# ECU_1.net
KiCad netlist of a schematic drawn in EAGLE
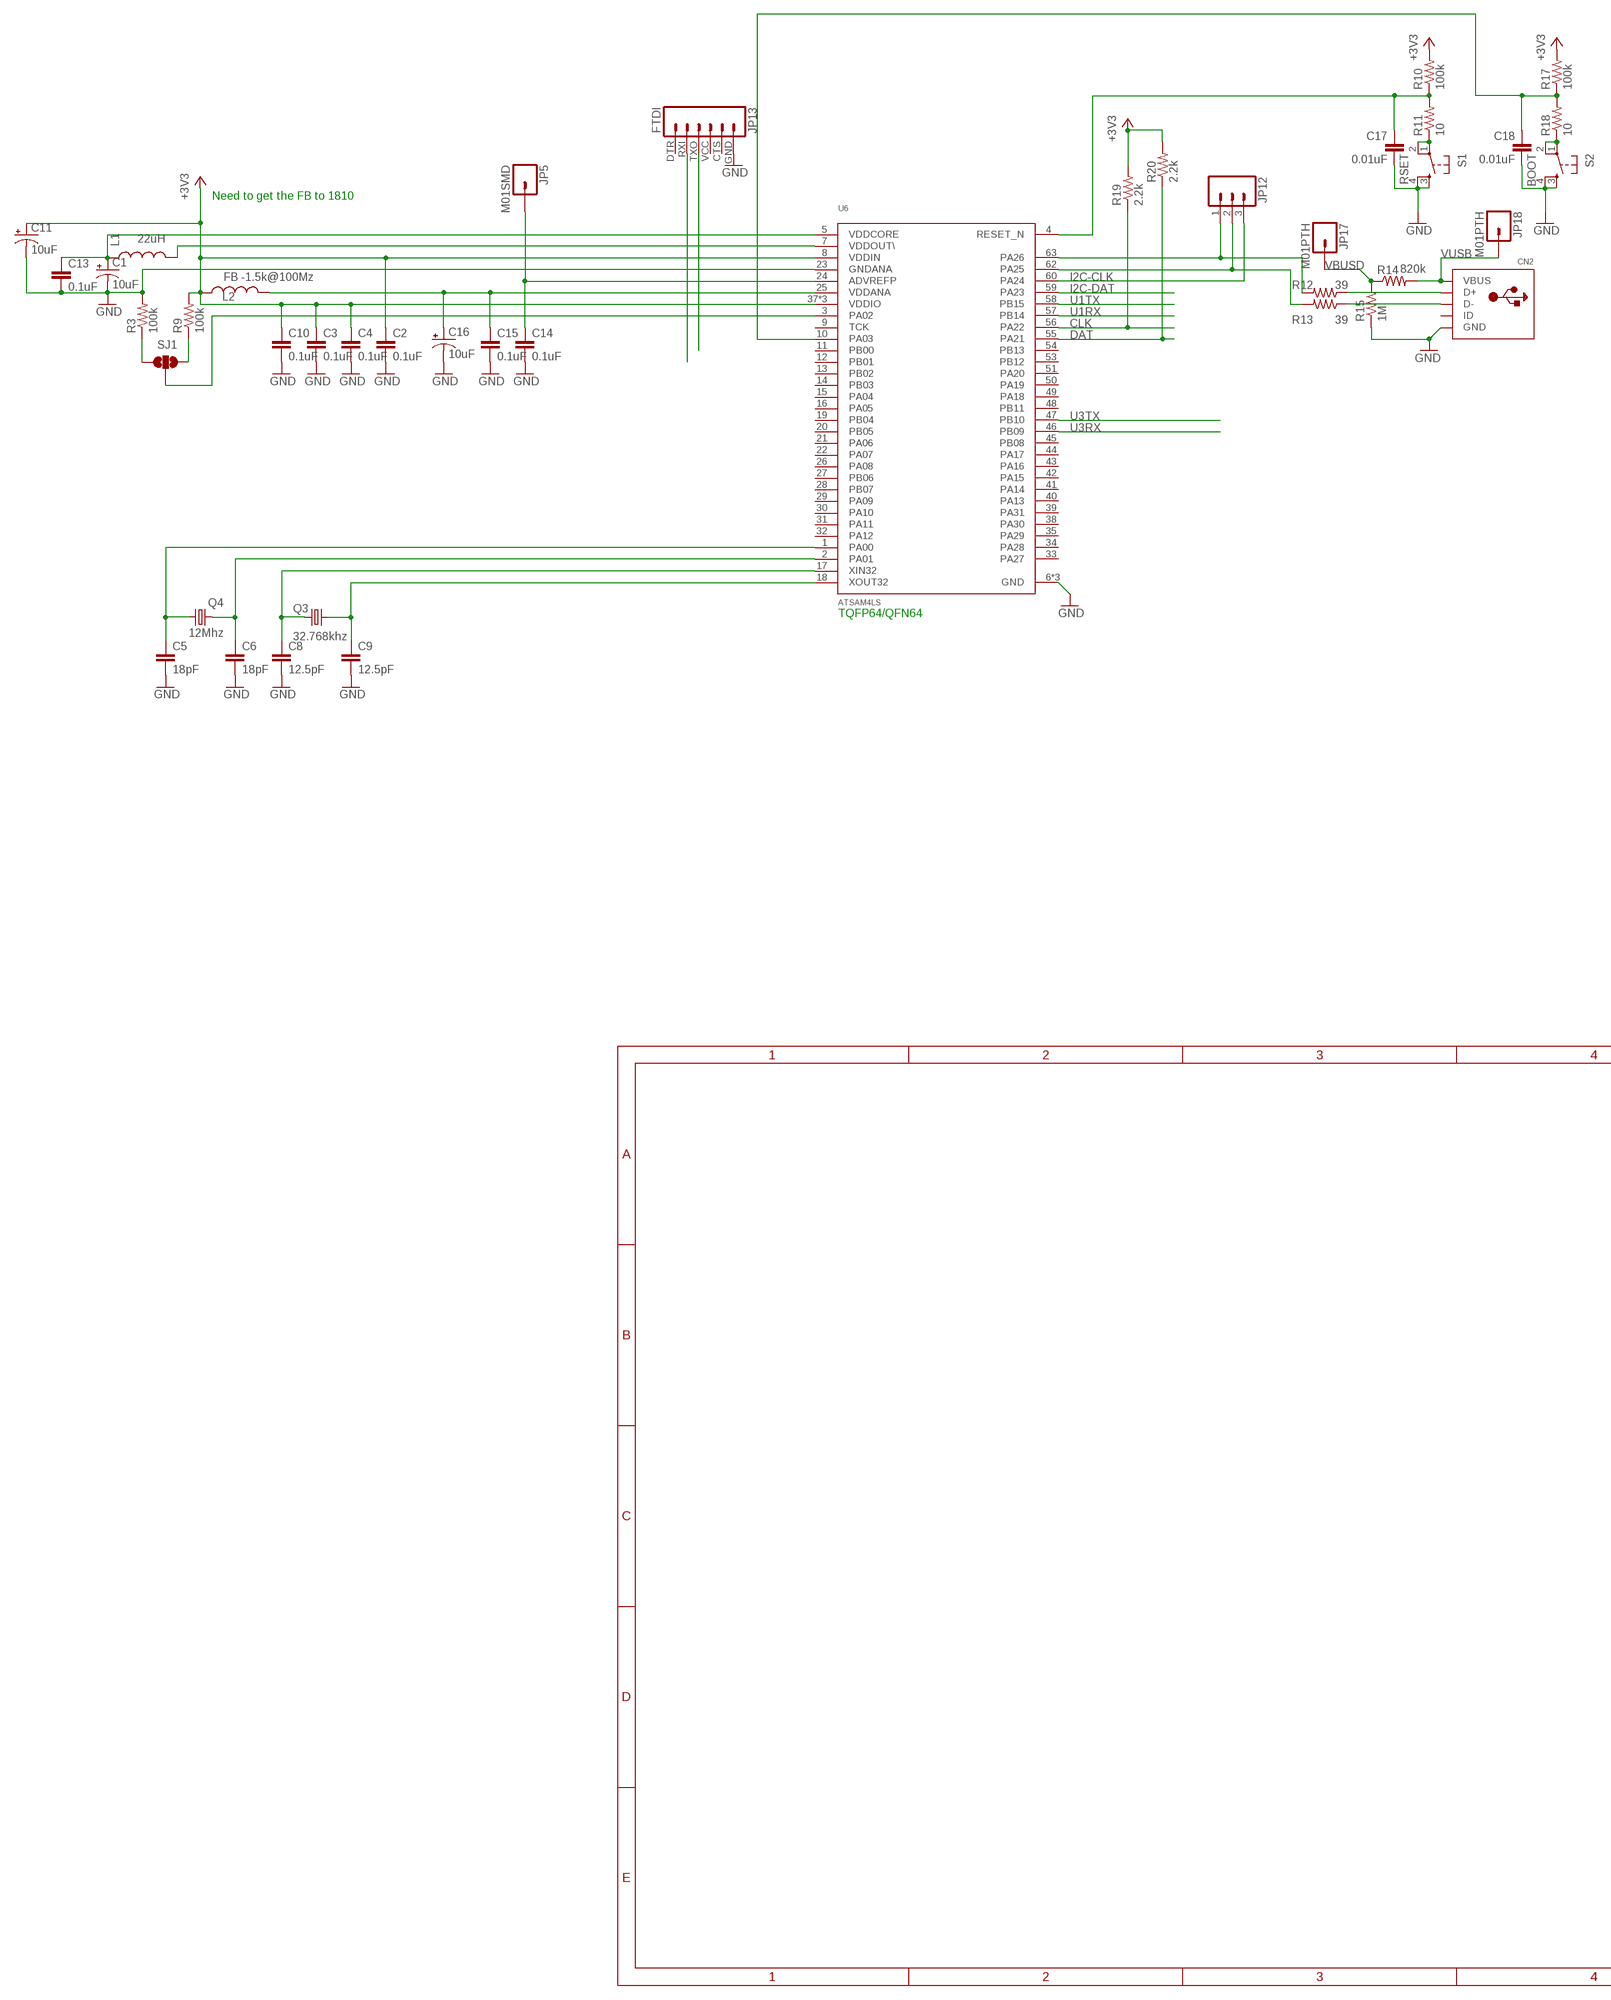
[diagram p0: schematic, sheet 1, part 1 of 2]
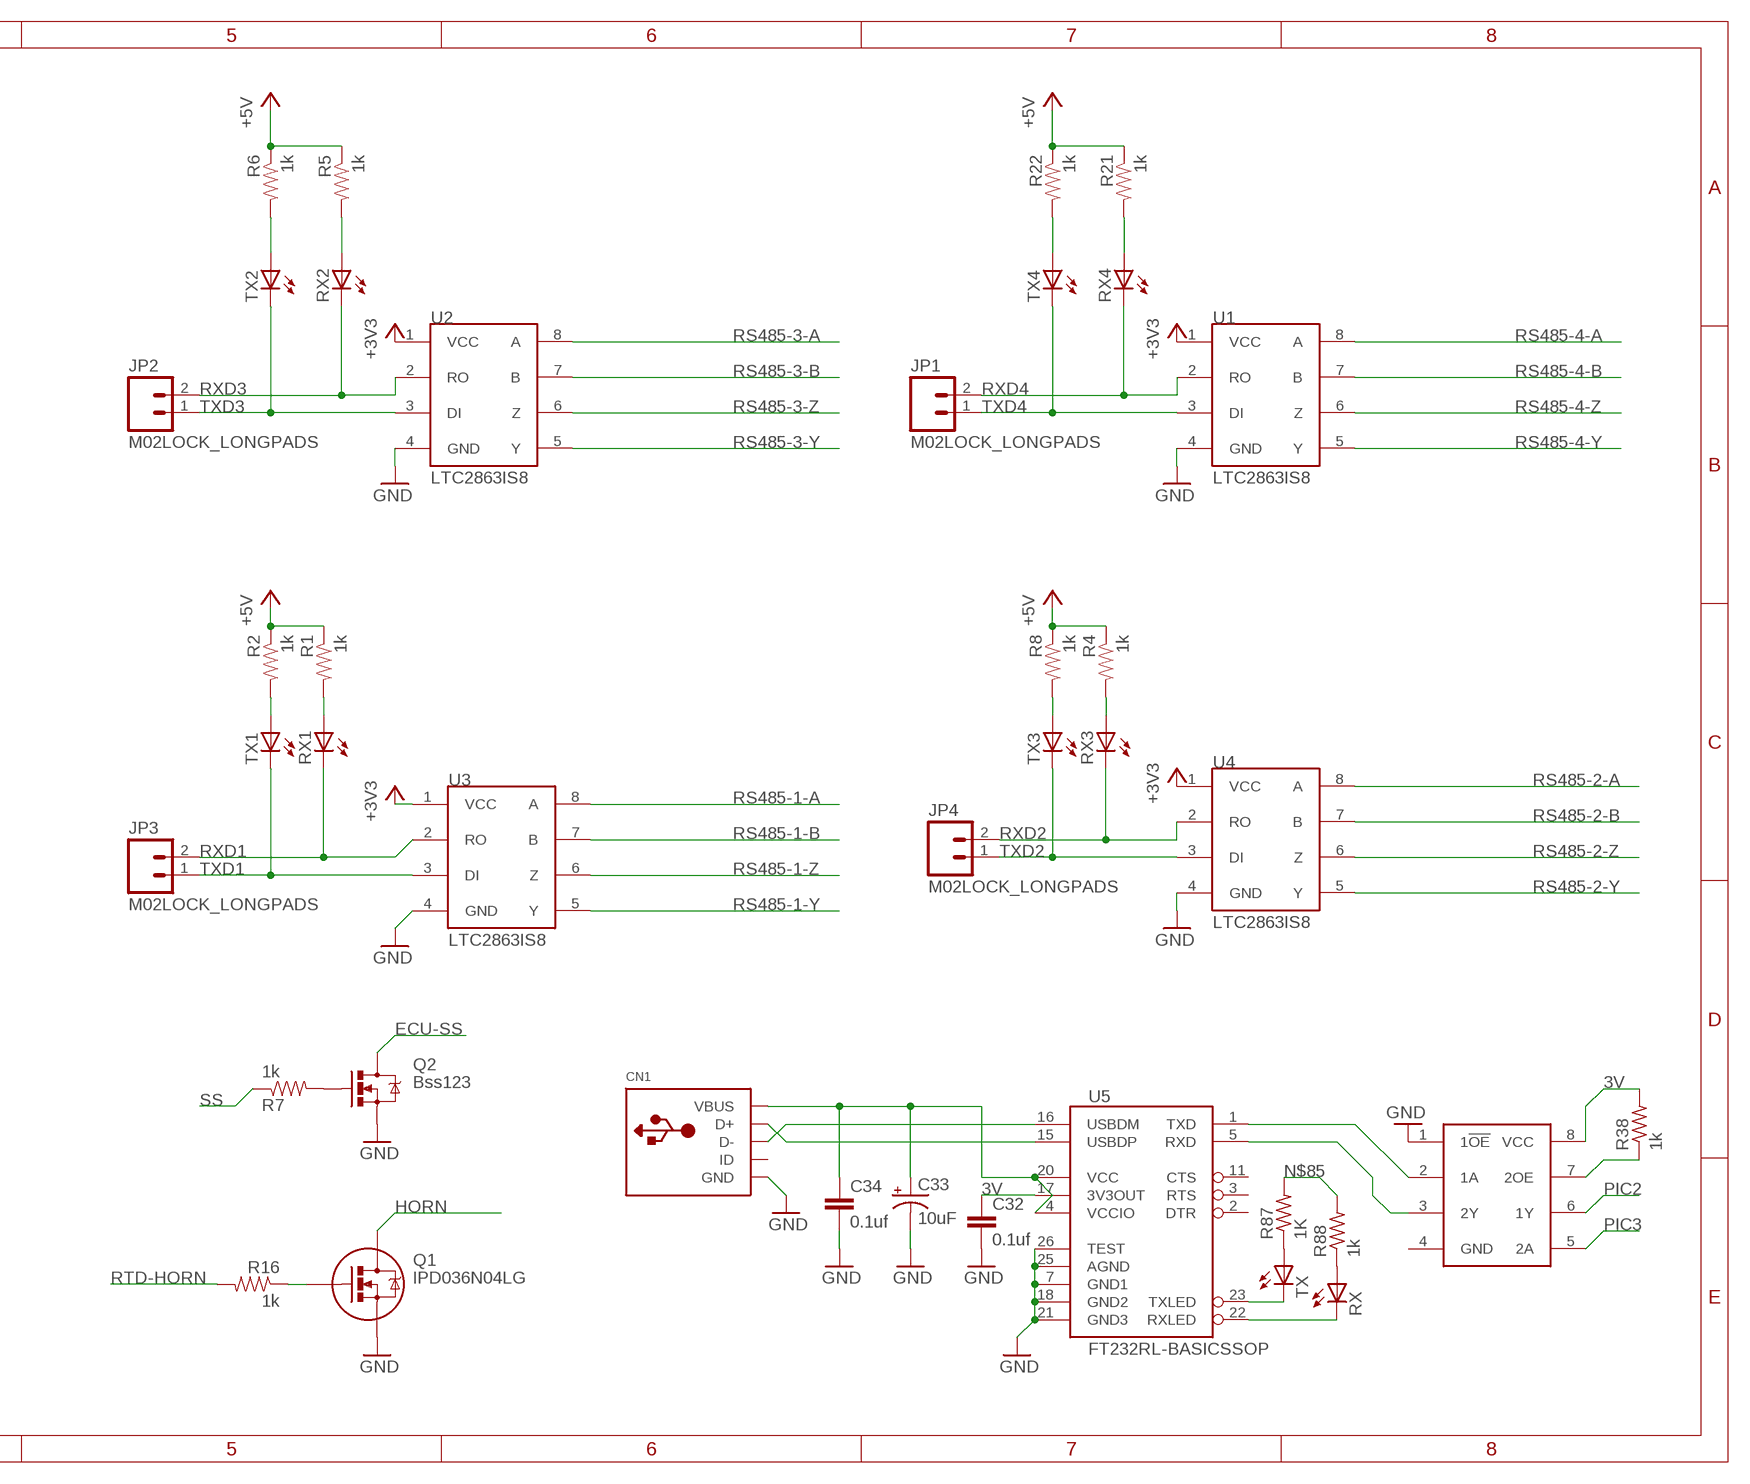
[diagram p1: schematic, sheet 1, part 2 of 2]
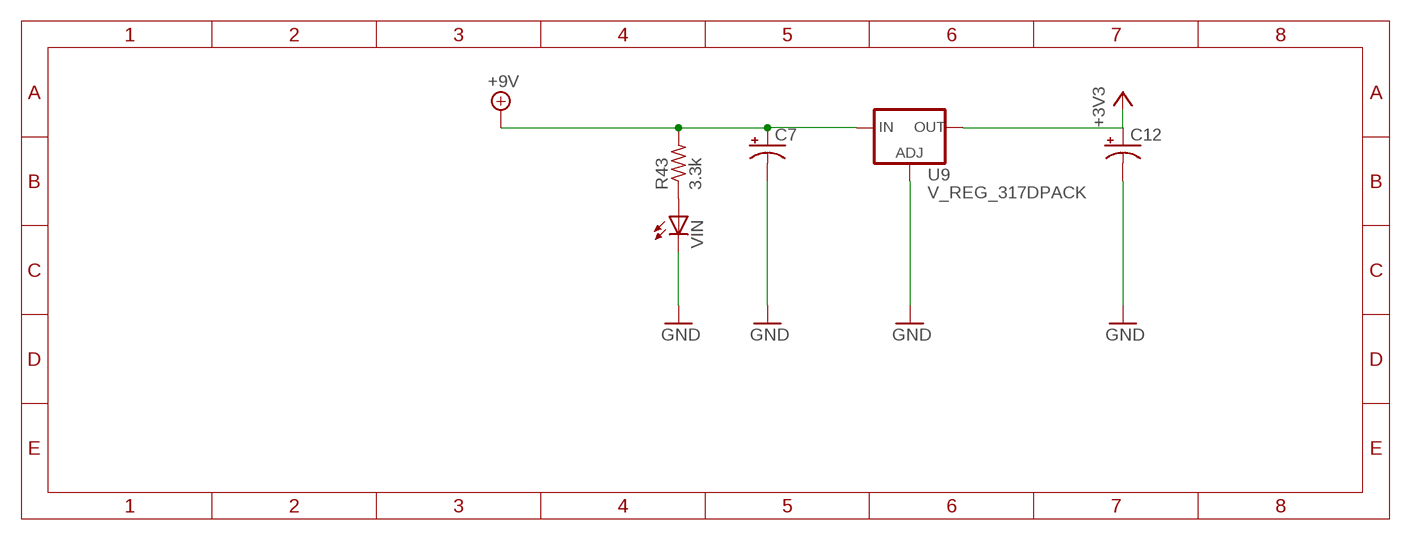
[diagram p2: schematic, sheet 2]
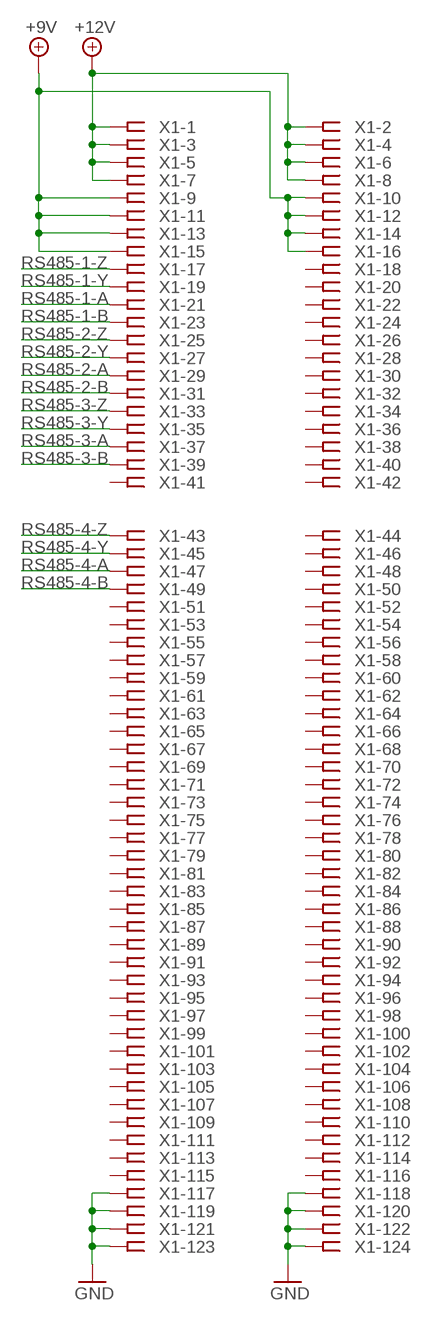
[diagram p3: schematic, sheet 3]

(export (version "E")
  (design (tool "Eeschema 10.0.6"))
  (components
    (comp (ref "C1")
      (value "10uF")
      (footprint "eagle-import:EIA3216")
      (libsource (lib "eagle-import") (part "SparkFun-Passives_CAP_POL1206"))
    )
    (comp (ref "C2")
      (value "0.1uF")
      (footprint "eagle-import:0805")
      (libsource (lib "eagle-import") (part "SparkFun-Passives_CAP0805"))
    )
    (comp (ref "C3")
      (value "0.1uF")
      (footprint "eagle-import:0805")
      (libsource (lib "eagle-import") (part "SparkFun-Passives_CAP0805"))
    )
    (comp (ref "C4")
      (value "0.1uF")
      (footprint "eagle-import:0805")
      (libsource (lib "eagle-import") (part "SparkFun-Passives_CAP0805"))
    )
    (comp (ref "C5")
      (value "18pF")
      (footprint "eagle-import:0805")
      (libsource (lib "eagle-import") (part "SparkFun-Passives_CAP0805"))
    )
    (comp (ref "C6")
      (value "18pF")
      (footprint "eagle-import:0805")
      (libsource (lib "eagle-import") (part "SparkFun-Passives_CAP0805"))
    )
    (comp (ref "C8")
      (value "12.5pF")
      (footprint "eagle-import:0805")
      (libsource (lib "eagle-import") (part "SparkFun-Passives_CAP0805"))
    )
    (comp (ref "C9")
      (value "12.5pF")
      (footprint "eagle-import:0805")
      (libsource (lib "eagle-import") (part "SparkFun-Passives_CAP0805"))
    )
    (comp (ref "C10")
      (value "0.1uF")
      (footprint "eagle-import:0805")
      (libsource (lib "eagle-import") (part "SparkFun-Passives_CAP0805"))
    )
    (comp (ref "C11")
      (value "10uF")
      (footprint "eagle-import:EIA3216")
      (libsource (lib "eagle-import") (part "10UF-16V-10%(TANT)"))
    )
    (comp (ref "C13")
      (value "0.1uF")
      (footprint "eagle-import:0805")
      (libsource (lib "eagle-import") (part "SparkFun-Passives_CAP0805"))
    )
    (comp (ref "C14")
      (value "0.1uF")
      (footprint "eagle-import:0805")
      (libsource (lib "eagle-import") (part "SparkFun-Passives_CAP0805"))
    )
    (comp (ref "C15")
      (value "0.1uF")
      (footprint "eagle-import:0805")
      (libsource (lib "eagle-import") (part "SparkFun-Passives_CAP0805"))
    )
    (comp (ref "C16")
      (value "10uF")
      (footprint "eagle-import:EIA3216")
      (libsource (lib "eagle-import") (part "SparkFun-Passives_CAP_POL1206"))
    )
    (comp (ref "C17")
      (value "0.01uF")
      (footprint "eagle-import:0805")
      (libsource (lib "eagle-import") (part "SparkFun-Passives_CAP0805"))
    )
    (comp (ref "C18")
      (value "0.01uF")
      (footprint "eagle-import:0805")
      (libsource (lib "eagle-import") (part "SparkFun-Passives_CAP0805"))
    )
    (comp (ref "C32")
      (value "0.1uf")
      (footprint "eagle-import:0805")
      (libsource (lib "eagle-import") (part "CAP0805"))
    )
    (comp (ref "C33")
      (value "10uF")
      (footprint "eagle-import:EIA3216")
      (libsource (lib "eagle-import") (part "CAP_POL1206"))
    )
    (comp (ref "C34")
      (value "0.1uf")
      (footprint "eagle-import:0805")
      (libsource (lib "eagle-import") (part "CAP0805"))
    )
    (comp (ref "CN1")
      (value "USBMOLEX")
      (footprint "eagle-import:USB-MINIB-THM-MOLEX")
      (libsource (lib "eagle-import") (part "USBMOLEX"))
    )
    (comp (ref "CN2")
      (value "USBMOLEX")
      (footprint "eagle-import:USB-MINIB-THM-MOLEX")
      (libsource (lib "eagle-import") (part "USBMOLEX"))
    )
    (comp (ref "JP1")
      (value "M02LOCK_LONGPADS")
      (footprint "eagle-import:1X02_LOCK_LONGPADS")
      (libsource (lib "eagle-import") (part "M02LOCK_LONGPADS"))
    )
    (comp (ref "JP2")
      (value "M02LOCK_LONGPADS")
      (footprint "eagle-import:1X02_LOCK_LONGPADS")
      (libsource (lib "eagle-import") (part "M02LOCK_LONGPADS"))
    )
    (comp (ref "JP3")
      (value "M02LOCK_LONGPADS")
      (footprint "eagle-import:1X02_LOCK_LONGPADS")
      (libsource (lib "eagle-import") (part "M02LOCK_LONGPADS"))
    )
    (comp (ref "JP4")
      (value "M02LOCK_LONGPADS")
      (footprint "eagle-import:1X02_LOCK_LONGPADS")
      (libsource (lib "eagle-import") (part "M02LOCK_LONGPADS"))
    )
    (comp (ref "JP5")
      (value "M01SMD")
      (footprint "eagle-import:LUXEON-PAD")
      (libsource (lib "eagle-import") (part "M01SMD"))
    )
    (comp (ref "JP12")
      (value "M03LOCK")
      (footprint "eagle-import:1X03_LOCK")
      (libsource (lib "eagle-import") (part "M03LOCK"))
    )
    (comp (ref "JP13")
      (value "FTDI")
      (footprint "eagle-import:FTDI_BASIC")
      (libsource (lib "eagle-import") (part "FTDI_BASICPTH"))
    )
    (comp (ref "JP17")
      (value "M01PTH")
      (footprint "eagle-import:1X01")
      (libsource (lib "eagle-import") (part "M01PTH"))
    )
    (comp (ref "JP18")
      (value "M01PTH")
      (footprint "eagle-import:1X01")
      (libsource (lib "eagle-import") (part "M01PTH"))
    )
    (comp (ref "L1")
      (value "22uH")
      (footprint "eagle-import:0805")
      (libsource (lib "eagle-import") (part "INDUCTOR0805"))
    )
    (comp (ref "L2")
      (value "FB -1.5k@100Mz")
      (footprint "eagle-import:0805")
      (libsource (lib "eagle-import") (part "INDUCTOR0805"))
    )
    (comp (ref "Q1")
      (value "IPD036N04LG")
      (footprint "eagle-import:TO-252")
      (libsource (lib "eagle-import") (part "IPD036N04LG"))
    )
    (comp (ref "Q2")
      (value "Bss123")
      (footprint "eagle-import:SOT23")
      (libsource (lib "eagle-import") (part "MOSFET-NCHANNELBSS123LT1G"))
    )
    (comp (ref "Q3")
      (value "32.768khz")
      (footprint "eagle-import:MM20SS")
      (libsource (lib "eagle-import") (part "CRYSTALMM20SS"))
    )
    (comp (ref "Q4")
      (value "12Mhz")
      (footprint "eagle-import:CTS406")
      (libsource (lib "eagle-import") (part "CRYSTALCTS406"))
    )
    (comp (ref "R1")
      (value "1k")
      (footprint "eagle-import:0805")
      (libsource (lib "eagle-import") (part "RESISTOR0805-RES"))
    )
    (comp (ref "R2")
      (value "1k")
      (footprint "eagle-import:0805")
      (libsource (lib "eagle-import") (part "RESISTOR0805-RES"))
    )
    (comp (ref "R3")
      (value "100k")
      (footprint "eagle-import:0805")
      (libsource (lib "eagle-import") (part "RESISTOR0805-RES"))
    )
    (comp (ref "R4")
      (value "1k")
      (footprint "eagle-import:0805")
      (libsource (lib "eagle-import") (part "RESISTOR0805-RES"))
    )
    (comp (ref "R5")
      (value "1k")
      (footprint "eagle-import:0805")
      (libsource (lib "eagle-import") (part "RESISTOR0805-RES"))
    )
    (comp (ref "R6")
      (value "1k")
      (footprint "eagle-import:0805")
      (libsource (lib "eagle-import") (part "RESISTOR0805-RES"))
    )
    (comp (ref "R7")
      (value "1k")
      (footprint "eagle-import:0805")
      (libsource (lib "eagle-import") (part "RESISTOR0805-RES"))
    )
    (comp (ref "R8")
      (value "1k")
      (footprint "eagle-import:0805")
      (libsource (lib "eagle-import") (part "RESISTOR0805-RES"))
    )
    (comp (ref "R9")
      (value "100k")
      (footprint "eagle-import:0805")
      (libsource (lib "eagle-import") (part "RESISTOR0805-RES"))
    )
    (comp (ref "R10")
      (value "100k")
      (footprint "eagle-import:0805")
      (libsource (lib "eagle-import") (part "RESISTOR0805-RES"))
    )
    (comp (ref "R11")
      (value "10")
      (footprint "eagle-import:0805")
      (libsource (lib "eagle-import") (part "RESISTOR0805-RES"))
    )
    (comp (ref "R12")
      (value "39")
      (footprint "eagle-import:0805")
      (libsource (lib "eagle-import") (part "RESISTOR0805-RES"))
    )
    (comp (ref "R13")
      (value "39")
      (footprint "eagle-import:0805")
      (libsource (lib "eagle-import") (part "RESISTOR0805-RES"))
    )
    (comp (ref "R14")
      (value "820k")
      (footprint "eagle-import:0805")
      (libsource (lib "eagle-import") (part "RESISTOR0805-RES"))
    )
    (comp (ref "R15")
      (value "1M")
      (footprint "eagle-import:0805")
      (libsource (lib "eagle-import") (part "RESISTOR0805-RES"))
    )
    (comp (ref "R16")
      (value "1k")
      (footprint "eagle-import:0805")
      (libsource (lib "eagle-import") (part "RESISTOR0805-RES"))
    )
    (comp (ref "R17")
      (value "100k")
      (footprint "eagle-import:0805")
      (libsource (lib "eagle-import") (part "RESISTOR0805-RES"))
    )
    (comp (ref "R18")
      (value "10")
      (footprint "eagle-import:0805")
      (libsource (lib "eagle-import") (part "RESISTOR0805-RES"))
    )
    (comp (ref "R19")
      (value "2.2k")
      (footprint "eagle-import:0805")
      (libsource (lib "eagle-import") (part "RESISTOR0805-RES"))
    )
    (comp (ref "R20")
      (value "2.2k")
      (footprint "eagle-import:0805")
      (libsource (lib "eagle-import") (part "RESISTOR0805-RES"))
    )
    (comp (ref "R21")
      (value "1k")
      (footprint "eagle-import:0805")
      (libsource (lib "eagle-import") (part "RESISTOR0805-RES"))
    )
    (comp (ref "R22")
      (value "1k")
      (footprint "eagle-import:0805")
      (libsource (lib "eagle-import") (part "RESISTOR0805-RES"))
    )
    (comp (ref "R38")
      (value "1k")
      (footprint "eagle-import:R0805")
      (libsource (lib "eagle-import") (part "R-US_R0805"))
    )
    (comp (ref "R87")
      (value "1K")
      (footprint "eagle-import:R0805")
      (libsource (lib "eagle-import") (part "R-US_R0805"))
    )
    (comp (ref "R88")
      (value "1k")
      (footprint "eagle-import:R0805")
      (libsource (lib "eagle-import") (part "R-US_R0805"))
    )
    (comp (ref "RX")
      (value "LEDCHIPLED_0805")
      (footprint "eagle-import:CHIPLED_0805")
      (libsource (lib "eagle-import") (part "LEDCHIPLED_0805"))
    )
    (comp (ref "RX1")
      (value "LEDCHIP-LED0805")
      (footprint "eagle-import:CHIP-LED0805")
      (libsource (lib "eagle-import") (part "LEDCHIP-LED0805"))
    )
    (comp (ref "RX2")
      (value "LEDCHIP-LED0805")
      (footprint "eagle-import:CHIP-LED0805")
      (libsource (lib "eagle-import") (part "LEDCHIP-LED0805"))
    )
    (comp (ref "RX3")
      (value "LEDCHIP-LED0805")
      (footprint "eagle-import:CHIP-LED0805")
      (libsource (lib "eagle-import") (part "LEDCHIP-LED0805"))
    )
    (comp (ref "RX4")
      (value "LEDCHIP-LED0805")
      (footprint "eagle-import:CHIP-LED0805")
      (libsource (lib "eagle-import") (part "LEDCHIP-LED0805"))
    )
    (comp (ref "S1")
      (value "RSET")
      (footprint "eagle-import:TACTILE-PTH")
      (libsource (lib "eagle-import") (part "TAC_SWITCHPTH"))
    )
    (comp (ref "S2")
      (value "BOOT")
      (footprint "eagle-import:TACTILE-PTH")
      (libsource (lib "eagle-import") (part "TAC_SWITCHPTH"))
    )
    (comp (ref "SJ1")
      (value "SOLDERJUMPER_2WAYS")
      (footprint "eagle-import:SJ_3")
      (libsource (lib "eagle-import") (part "SOLDERJUMPER_2WAYS"))
    )
    (comp (ref "TX")
      (value "LEDCHIPLED_0805")
      (footprint "eagle-import:CHIPLED_0805")
      (libsource (lib "eagle-import") (part "LEDCHIPLED_0805"))
    )
    (comp (ref "TX1")
      (value "LEDCHIP-LED0805")
      (footprint "eagle-import:CHIP-LED0805")
      (libsource (lib "eagle-import") (part "LEDCHIP-LED0805"))
    )
    (comp (ref "TX2")
      (value "LEDCHIP-LED0805")
      (footprint "eagle-import:CHIP-LED0805")
      (libsource (lib "eagle-import") (part "LEDCHIP-LED0805"))
    )
    (comp (ref "TX3")
      (value "LEDCHIP-LED0805")
      (footprint "eagle-import:CHIP-LED0805")
      (libsource (lib "eagle-import") (part "LEDCHIP-LED0805"))
    )
    (comp (ref "TX4")
      (value "LEDCHIP-LED0805")
      (footprint "eagle-import:CHIP-LED0805")
      (libsource (lib "eagle-import") (part "LEDCHIP-LED0805"))
    )
    (comp (ref "U1")
      (value "LTC2863IS8")
      (footprint "eagle-import:SO08")
      (libsource (lib "eagle-import") (part "ISL83077"))
    )
    (comp (ref "U2")
      (value "LTC2863IS8")
      (footprint "eagle-import:SO08")
      (libsource (lib "eagle-import") (part "ISL83077"))
    )
    (comp (ref "U3")
      (value "LTC2863IS8")
      (footprint "eagle-import:SO08")
      (libsource (lib "eagle-import") (part "ISL83077"))
    )
    (comp (ref "U4")
      (value "LTC2863IS8")
      (footprint "eagle-import:SO08")
      (libsource (lib "eagle-import") (part "ISL83077"))
    )
    (comp (ref "U5")
      (value "FT232RL-BASICSSOP")
      (footprint "eagle-import:SSOP28DB")
      (libsource (lib "eagle-import") (part "FT232RL-BASICSSOP"))
    )
    (comp (ref "U6")
      (value "ATSAM4LS")
      (footprint "eagle-import:TQFP-64")
      (libsource (lib "eagle-import") (part "SAM4L"))
    )
    (comp (ref "U14")
      (value "SN74LVC2G241DCTR")
      (footprint "eagle-import:VFSOP-8")
      (libsource (lib "eagle-import") (part "SN74LVC2G241DCTR"))
    )
    (comp (ref "C7")
      (value "CAP_POL7343")
      (footprint "eagle-import:EIA7343")
      (libsource (lib "eagle-import") (part "SparkFun-Capacitors_CAP_POL7343"))
    )
    (comp (ref "C12")
      (value "CAP_POL3528")
      (footprint "eagle-import:EIA3528")
      (libsource (lib "eagle-import") (part "SparkFun-Capacitors_CAP_POL3528"))
    )
    (comp (ref "R43")
      (value "3.3k")
      (footprint "eagle-import:R0805")
      (libsource (lib "eagle-import") (part "R-US_R0805"))
    )
    (comp (ref "U9")
      (value "V_REG_317DPACK")
      (footprint "eagle-import:V-REG_DPACK")
      (libsource (lib "eagle-import") (part "V_REG_317DPACK"))
    )
    (comp (ref "VIN")
      (value "LEDCHIP-LED0805")
      (footprint "eagle-import:CHIP-LED0805")
      (libsource (lib "eagle-import") (part "LEDCHIP-LED0805"))
    )
    (comp (ref "X1")
      (value "AGP-3X3")
      (footprint "eagle-import:AGP-3X3")
      (libsource (lib "eagle-import") (part "AGP-3X3"))
    )
  )
  (nets
    (net (code "1") (name "+3V3") (class "Default")
      (node (ref "C10") (pin "1") (pinfunction "1_1") (pintype "passive"))
      (node (ref "C11") (pin "A") (pinfunction "+_A") (pintype "passive"))
      (node (ref "C12") (pin "A") (pinfunction "+_A") (pintype "passive"))
      (node (ref "C2") (pin "1") (pinfunction "1_1") (pintype "passive"))
      (node (ref "C3") (pin "1") (pinfunction "1_1") (pintype "passive"))
      (node (ref "C4") (pin "1") (pinfunction "1_1") (pintype "passive"))
      (node (ref "L2") (pin "1") (pinfunction "1_1") (pintype "passive"))
      (node (ref "R10") (pin "2") (pinfunction "2_2") (pintype "passive"))
      (node (ref "R17") (pin "2") (pinfunction "2_2") (pintype "passive"))
      (node (ref "R19") (pin "2") (pinfunction "2_2") (pintype "passive"))
      (node (ref "R20") (pin "2") (pinfunction "2_2") (pintype "passive"))
      (node (ref "R9") (pin "2") (pinfunction "2_2") (pintype "passive"))
      (node (ref "U1") (pin "1") (pinfunction "VCC_1") (pintype "bidirectional"))
      (node (ref "U2") (pin "1") (pinfunction "VCC_1") (pintype "bidirectional"))
      (node (ref "U3") (pin "1") (pinfunction "VCC_1") (pintype "bidirectional"))
      (node (ref "U4") (pin "1") (pinfunction "VCC_1") (pintype "bidirectional"))
      (node (ref "U6") (pin "37") (pinfunction "VDDIO_37") (pintype "bidirectional"))
      (node (ref "U6") (pin "52") (pinfunction "VDDIO_52") (pintype "bidirectional"))
      (node (ref "U6") (pin "61") (pinfunction "VDDIO_61") (pintype "bidirectional"))
      (node (ref "U6") (pin "8") (pinfunction "VDDIN_8") (pintype "bidirectional"))
      (node (ref "U9") (pin "4") (pinfunction "OUT_4") (pintype "output"))
    )
    (net (code "2") (name "+5V") (class "Default")
      (node (ref "R1") (pin "1") (pinfunction "1_1") (pintype "passive"))
      (node (ref "R2") (pin "1") (pinfunction "1_1") (pintype "passive"))
      (node (ref "R21") (pin "1") (pinfunction "1_1") (pintype "passive"))
      (node (ref "R22") (pin "1") (pinfunction "1_1") (pintype "passive"))
      (node (ref "R4") (pin "1") (pinfunction "1_1") (pintype "passive"))
      (node (ref "R5") (pin "1") (pinfunction "1_1") (pintype "passive"))
      (node (ref "R6") (pin "1") (pinfunction "1_1") (pintype "passive"))
      (node (ref "R8") (pin "1") (pinfunction "1_1") (pintype "passive"))
    )
    (net (code "3") (name "+9V") (class "Default")
      (node (ref "C7") (pin "A") (pinfunction "+_A") (pintype "passive"))
      (node (ref "R43") (pin "2") (pinfunction "2_2") (pintype "passive"))
      (node (ref "U9") (pin "3") (pinfunction "IN_3") (pintype "input"))
      (node (ref "X1") (pin "10") (pinfunction "P_10") (pintype "passive"))
      (node (ref "X1") (pin "11") (pinfunction "P_11") (pintype "passive"))
      (node (ref "X1") (pin "12") (pinfunction "P_12") (pintype "passive"))
      (node (ref "X1") (pin "13") (pinfunction "P_13") (pintype "passive"))
      (node (ref "X1") (pin "14") (pinfunction "P_14") (pintype "passive"))
      (node (ref "X1") (pin "15") (pinfunction "P_15") (pintype "passive"))
      (node (ref "X1") (pin "16") (pinfunction "P_16") (pintype "passive"))
      (node (ref "X1") (pin "9") (pinfunction "P_9") (pintype "passive"))
    )
    (net (code "4") (name "+12V") (class "Default")
      (node (ref "X1") (pin "1") (pinfunction "P_1") (pintype "passive"))
      (node (ref "X1") (pin "2") (pinfunction "P_2") (pintype "passive"))
      (node (ref "X1") (pin "3") (pinfunction "P_3") (pintype "passive"))
      (node (ref "X1") (pin "4") (pinfunction "P_4") (pintype "passive"))
      (node (ref "X1") (pin "5") (pinfunction "P_5") (pintype "passive"))
      (node (ref "X1") (pin "6") (pinfunction "P_6") (pintype "passive"))
      (node (ref "X1") (pin "7") (pinfunction "P_7") (pintype "passive"))
      (node (ref "X1") (pin "8") (pinfunction "P_8") (pintype "passive"))
    )
    (net (code "5") (name "3V") (class "Default")
      (node (ref "C32") (pin "1") (pinfunction "1_1") (pintype "passive"))
      (node (ref "R38") (pin "2") (pinfunction "2_2") (pintype "passive"))
      (node (ref "U14") (pin "8") (pinfunction "VCC_8") (pintype "bidirectional"))
      (node (ref "U5") (pin "17") (pinfunction "3V3OUT_17") (pintype "output"))
    )
    (net (code "6") (name "CLK") (class "Default")
      (node (ref "R19") (pin "1") (pinfunction "1_1") (pintype "passive"))
      (node (ref "U6") (pin "56") (pinfunction "PA22_56") (pintype "bidirectional"))
    )
    (net (code "7") (name "DAT") (class "Default")
      (node (ref "R20") (pin "1") (pinfunction "1_1") (pintype "passive"))
      (node (ref "U6") (pin "55") (pinfunction "PA21_55") (pintype "bidirectional"))
    )
    (net (code "8") (name "ECU-SS") (class "Default")
      (node (ref "Q2") (pin "3") (pinfunction "D_3") (pintype "passive"))
    )
    (net (code "9") (name "GND") (class "Default")
      (node (ref "C1") (pin "C") (pinfunction "-_C") (pintype "passive"))
      (node (ref "C10") (pin "2") (pinfunction "2_2") (pintype "passive"))
      (node (ref "C11") (pin "C") (pinfunction "-_C") (pintype "passive"))
      (node (ref "C12") (pin "C") (pinfunction "-_C") (pintype "passive"))
      (node (ref "C13") (pin "2") (pinfunction "2_2") (pintype "passive"))
      (node (ref "C14") (pin "2") (pinfunction "2_2") (pintype "passive"))
      (node (ref "C15") (pin "2") (pinfunction "2_2") (pintype "passive"))
      (node (ref "C16") (pin "C") (pinfunction "-_C") (pintype "passive"))
      (node (ref "C17") (pin "2") (pinfunction "2_2") (pintype "passive"))
      (node (ref "C18") (pin "2") (pinfunction "2_2") (pintype "passive"))
      (node (ref "C2") (pin "2") (pinfunction "2_2") (pintype "passive"))
      (node (ref "C3") (pin "2") (pinfunction "2_2") (pintype "passive"))
      (node (ref "C32") (pin "2") (pinfunction "2_2") (pintype "passive"))
      (node (ref "C33") (pin "C") (pinfunction "-_C") (pintype "passive"))
      (node (ref "C34") (pin "2") (pinfunction "2_2") (pintype "passive"))
      (node (ref "C4") (pin "2") (pinfunction "2_2") (pintype "passive"))
      (node (ref "C5") (pin "2") (pinfunction "2_2") (pintype "passive"))
      (node (ref "C6") (pin "2") (pinfunction "2_2") (pintype "passive"))
      (node (ref "C7") (pin "C") (pinfunction "-_C") (pintype "passive"))
      (node (ref "C8") (pin "2") (pinfunction "2_2") (pintype "passive"))
      (node (ref "C9") (pin "2") (pinfunction "2_2") (pintype "passive"))
      (node (ref "CN1") (pin "GND") (pinfunction "GND_GND") (pintype "power_in"))
      (node (ref "CN2") (pin "GND") (pinfunction "GND_GND") (pintype "power_in"))
      (node (ref "JP13") (pin "GND") (pinfunction "6_GND") (pintype "passive"))
      (node (ref "Q1") (pin "3") (pinfunction "S_3") (pintype "passive"))
      (node (ref "Q2") (pin "2") (pinfunction "S_2") (pintype "passive"))
      (node (ref "R15") (pin "1") (pinfunction "1_1") (pintype "passive"))
      (node (ref "R3") (pin "2") (pinfunction "2_2") (pintype "passive"))
      (node (ref "S1") (pin "3") (pinfunction "3_3") (pintype "passive"))
      (node (ref "S1") (pin "4") (pinfunction "4_4") (pintype "passive"))
      (node (ref "S2") (pin "3") (pinfunction "3_3") (pintype "passive"))
      (node (ref "S2") (pin "4") (pinfunction "4_4") (pintype "passive"))
      (node (ref "U1") (pin "4") (pinfunction "GND_4") (pintype "bidirectional"))
      (node (ref "U14") (pin "1") (pinfunction "1~{OE}_1") (pintype "bidirectional"))
      (node (ref "U2") (pin "4") (pinfunction "GND_4") (pintype "bidirectional"))
      (node (ref "U3") (pin "4") (pinfunction "GND_4") (pintype "bidirectional"))
      (node (ref "U4") (pin "4") (pinfunction "GND_4") (pintype "bidirectional"))
      (node (ref "U5") (pin "18") (pinfunction "GND2_18") (pintype "power_in"))
      (node (ref "U5") (pin "21") (pinfunction "GND3_21") (pintype "power_in"))
      (node (ref "U5") (pin "25") (pinfunction "AGND_25") (pintype "power_in"))
      (node (ref "U5") (pin "26") (pinfunction "TEST_26") (pintype "input"))
      (node (ref "U5") (pin "7") (pinfunction "GND1_7") (pintype "power_in"))
      (node (ref "U6") (pin "23") (pinfunction "GNDANA_23") (pintype "bidirectional"))
      (node (ref "U6") (pin "36") (pinfunction "GND_36") (pintype "bidirectional"))
      (node (ref "U6") (pin "6") (pinfunction "GND_6") (pintype "bidirectional"))
      (node (ref "U6") (pin "64") (pinfunction "GND_64") (pintype "bidirectional"))
      (node (ref "U9") (pin "1") (pinfunction "ADJ_1") (pintype "input"))
      (node (ref "VIN") (pin "C") (pinfunction "C_C") (pintype "passive"))
      (node (ref "X1") (pin "117") (pinfunction "P_117") (pintype "passive"))
      (node (ref "X1") (pin "118") (pinfunction "P_118") (pintype "passive"))
      (node (ref "X1") (pin "119") (pinfunction "P_119") (pintype "passive"))
      (node (ref "X1") (pin "120") (pinfunction "P_120") (pintype "passive"))
      (node (ref "X1") (pin "121") (pinfunction "P_121") (pintype "passive"))
      (node (ref "X1") (pin "122") (pinfunction "P_122") (pintype "passive"))
      (node (ref "X1") (pin "123") (pinfunction "P_123") (pintype "passive"))
      (node (ref "X1") (pin "124") (pinfunction "P_124") (pintype "passive"))
    )
    (net (code "10") (name "HORN") (class "Default")
      (node (ref "Q1") (pin "2") (pinfunction "D_2") (pintype "passive"))
    )
    (net (code "11") (name "I2C-CLK") (class "Default")
      (node (ref "JP12") (pin "3") (pinfunction "3_3") (pintype "passive"))
      (node (ref "U6") (pin "60") (pinfunction "PA24_60") (pintype "bidirectional"))
    )
    (net (code "12") (name "I2C-DAT") (class "Default")
      (node (ref "U6") (pin "59") (pinfunction "PA23_59") (pintype "bidirectional"))
    )
    (net (code "13") (name "N$85") (class "Default")
      (node (ref "C33") (pin "A") (pinfunction "+_A") (pintype "passive"))
      (node (ref "C34") (pin "1") (pinfunction "1_1") (pintype "passive"))
      (node (ref "CN1") (pin "VBUS") (pinfunction "VBUS_VBUS") (pintype "power_in"))
      (node (ref "R87") (pin "2") (pinfunction "2_2") (pintype "passive"))
      (node (ref "R88") (pin "2") (pinfunction "2_2") (pintype "passive"))
      (node (ref "U5") (pin "20") (pinfunction "VCC_20") (pintype "power_in"))
      (node (ref "U5") (pin "4") (pinfunction "VCCIO_4") (pintype "power_in"))
    )
    (net (code "14") (name "Net-(C1-+)") (class "Default")
      (node (ref "C1") (pin "A") (pinfunction "+_A") (pintype "passive"))
      (node (ref "C13") (pin "1") (pinfunction "1_1") (pintype "passive"))
      (node (ref "L1") (pin "1") (pinfunction "1_1") (pintype "passive"))
      (node (ref "U6") (pin "5") (pinfunction "VDDCORE_5") (pintype "bidirectional"))
    )
    (net (code "15") (name "Net-(C16-+)") (class "Default")
      (node (ref "C15") (pin "1") (pinfunction "1_1") (pintype "passive"))
      (node (ref "C16") (pin "A") (pinfunction "+_A") (pintype "passive"))
      (node (ref "L2") (pin "2") (pinfunction "2_2") (pintype "passive"))
      (node (ref "U6") (pin "25") (pinfunction "VDDANA_25") (pintype "bidirectional"))
    )
    (net (code "16") (name "Net-(CN2-PadD+)") (class "Default")
      (node (ref "CN2") (pin "D+") (pinfunction "D+_D+") (pintype "bidirectional"))
      (node (ref "R12") (pin "1") (pinfunction "1_1") (pintype "passive"))
    )
    (net (code "17") (name "Net-(CN2-PadD-)") (class "Default")
      (node (ref "CN2") (pin "D-") (pinfunction "D-_D-") (pintype "bidirectional"))
      (node (ref "R13") (pin "1") (pinfunction "1_1") (pintype "passive"))
    )
    (net (code "18") (name "Net-(JP5-1)") (class "Default")
      (node (ref "C14") (pin "1") (pinfunction "1_1") (pintype "passive"))
      (node (ref "JP5") (pin "P$1") (pinfunction "1_P$1") (pintype "passive"))
      (node (ref "U6") (pin "24") (pinfunction "ADVREFP_24") (pintype "bidirectional"))
    )
    (net (code "19") (name "Net-(Q1-G)") (class "Default")
      (node (ref "Q1") (pin "1") (pinfunction "G_1") (pintype "passive"))
      (node (ref "R16") (pin "1") (pinfunction "1_1") (pintype "passive"))
    )
    (net (code "20") (name "Net-(Q2-G)") (class "Default")
      (node (ref "Q2") (pin "1") (pinfunction "G_1") (pintype "passive"))
      (node (ref "R7") (pin "2") (pinfunction "2_2") (pintype "passive"))
    )
    (net (code "21") (name "Net-(Q3-2)") (class "Default")
      (node (ref "C9") (pin "1") (pinfunction "1_1") (pintype "passive"))
      (node (ref "Q3") (pin "4") (pinfunction "2_4") (pintype "passive"))
      (node (ref "U6") (pin "18") (pinfunction "XOUT32_18") (pintype "bidirectional"))
    )
    (net (code "22") (name "Net-(Q4-2)") (class "Default")
      (node (ref "C5") (pin "1") (pinfunction "1_1") (pintype "passive"))
      (node (ref "Q4") (pin "3") (pinfunction "2_3") (pintype "passive"))
      (node (ref "U6") (pin "1") (pinfunction "PA00_1") (pintype "bidirectional"))
    )
    (net (code "23") (name "Net-(R1-Pad2)") (class "Default")
      (node (ref "R1") (pin "2") (pinfunction "2_2") (pintype "passive"))
      (node (ref "RX1") (pin "A") (pinfunction "A_A") (pintype "passive"))
    )
    (net (code "24") (name "Net-(R2-Pad2)") (class "Default")
      (node (ref "R2") (pin "2") (pinfunction "2_2") (pintype "passive"))
      (node (ref "TX1") (pin "A") (pinfunction "A_A") (pintype "passive"))
    )
    (net (code "25") (name "Net-(R3-Pad1)") (class "Default")
      (node (ref "R3") (pin "1") (pinfunction "1_1") (pintype "passive"))
      (node (ref "SJ1") (pin "3") (pinfunction "3_3") (pintype "passive"))
    )
    (net (code "26") (name "Net-(R4-Pad2)") (class "Default")
      (node (ref "R4") (pin "2") (pinfunction "2_2") (pintype "passive"))
      (node (ref "RX3") (pin "A") (pinfunction "A_A") (pintype "passive"))
    )
    (net (code "27") (name "Net-(R5-Pad2)") (class "Default")
      (node (ref "R5") (pin "2") (pinfunction "2_2") (pintype "passive"))
      (node (ref "RX2") (pin "A") (pinfunction "A_A") (pintype "passive"))
    )
    (net (code "28") (name "Net-(R6-Pad2)") (class "Default")
      (node (ref "R6") (pin "2") (pinfunction "2_2") (pintype "passive"))
      (node (ref "TX2") (pin "A") (pinfunction "A_A") (pintype "passive"))
    )
    (net (code "29") (name "Net-(R8-Pad2)") (class "Default")
      (node (ref "R8") (pin "2") (pinfunction "2_2") (pintype "passive"))
      (node (ref "TX3") (pin "A") (pinfunction "A_A") (pintype "passive"))
    )
    (net (code "30") (name "Net-(R9-Pad1)") (class "Default")
      (node (ref "R9") (pin "1") (pinfunction "1_1") (pintype "passive"))
      (node (ref "SJ1") (pin "1") (pinfunction "1_1") (pintype "passive"))
    )
    (net (code "31") (name "Net-(R11-Pad1)") (class "Default")
      (node (ref "R11") (pin "1") (pinfunction "1_1") (pintype "passive"))
      (node (ref "S1") (pin "1") (pinfunction "1_1") (pintype "passive"))
      (node (ref "S1") (pin "2") (pinfunction "2_2") (pintype "passive"))
    )
    (net (code "32") (name "Net-(R18-Pad1)") (class "Default")
      (node (ref "R18") (pin "1") (pinfunction "1_1") (pintype "passive"))
      (node (ref "S2") (pin "1") (pinfunction "1_1") (pintype "passive"))
      (node (ref "S2") (pin "2") (pinfunction "2_2") (pintype "passive"))
    )
    (net (code "33") (name "Net-(R21-Pad2)") (class "Default")
      (node (ref "R21") (pin "2") (pinfunction "2_2") (pintype "passive"))
      (node (ref "RX4") (pin "A") (pinfunction "A_A") (pintype "passive"))
    )
    (net (code "34") (name "Net-(R22-Pad2)") (class "Default")
      (node (ref "R22") (pin "2") (pinfunction "2_2") (pintype "passive"))
      (node (ref "TX4") (pin "A") (pinfunction "A_A") (pintype "passive"))
    )
    (net (code "35") (name "Net-(R43-Pad1)") (class "Default")
      (node (ref "R43") (pin "1") (pinfunction "1_1") (pintype "passive"))
      (node (ref "VIN") (pin "A") (pinfunction "A_A") (pintype "passive"))
    )
    (net (code "36") (name "Net-(R87-Pad1)") (class "Default")
      (node (ref "R87") (pin "1") (pinfunction "1_1") (pintype "passive"))
      (node (ref "TX") (pin "A") (pinfunction "A_A") (pintype "passive"))
    )
    (net (code "37") (name "Net-(R88-Pad1)") (class "Default")
      (node (ref "R88") (pin "1") (pinfunction "1_1") (pintype "passive"))
      (node (ref "RX") (pin "A") (pinfunction "A_A") (pintype "passive"))
    )
    (net (code "38") (name "Net-(U5-RXLED)") (class "Default")
      (node (ref "RX") (pin "C") (pinfunction "C_C") (pintype "passive"))
      (node (ref "U5") (pin "22") (pinfunction "RXLED_22") (pintype "bidirectional"))
    )
    (net (code "39") (name "Net-(U5-TXLED)") (class "Default")
      (node (ref "TX") (pin "C") (pinfunction "C_C") (pintype "passive"))
      (node (ref "U5") (pin "23") (pinfunction "TXLED_23") (pintype "bidirectional"))
    )
    (net (code "40") (name "Net-(U5-USBDM)") (class "Default")
      (node (ref "CN1") (pin "D-") (pinfunction "D-_D-") (pintype "bidirectional"))
      (node (ref "U5") (pin "16") (pinfunction "USBDM_16") (pintype "bidirectional"))
    )
    (net (code "41") (name "Net-(U5-USBDP)") (class "Default")
      (node (ref "CN1") (pin "D+") (pinfunction "D+_D+") (pintype "bidirectional"))
      (node (ref "U5") (pin "15") (pinfunction "USBDP_15") (pintype "bidirectional"))
    )
    (net (code "42") (name "Net-(U6-PA01)") (class "Default")
      (node (ref "C6") (pin "1") (pinfunction "1_1") (pintype "passive"))
      (node (ref "Q4") (pin "1") (pinfunction "1_1") (pintype "passive"))
      (node (ref "U6") (pin "2") (pinfunction "PA01_2") (pintype "bidirectional"))
    )
    (net (code "43") (name "Net-(U6-PA02)") (class "Default")
      (node (ref "SJ1") (pin "2") (pinfunction "2_2") (pintype "passive"))
      (node (ref "U6") (pin "3") (pinfunction "PA02_3") (pintype "bidirectional"))
    )
    (net (code "44") (name "Net-(U6-PA03)") (class "Default")
      (node (ref "C18") (pin "1") (pinfunction "1_1") (pintype "passive"))
      (node (ref "R17") (pin "1") (pinfunction "1_1") (pintype "passive"))
      (node (ref "R18") (pin "2") (pinfunction "2_2") (pintype "passive"))
      (node (ref "U6") (pin "10") (pinfunction "PA03_10") (pintype "bidirectional"))
    )
    (net (code "45") (name "Net-(U6-PA25)") (class "Default")
      (node (ref "JP12") (pin "2") (pinfunction "2_2") (pintype "passive"))
      (node (ref "R13") (pin "2") (pinfunction "2_2") (pintype "passive"))
      (node (ref "U6") (pin "62") (pinfunction "PA25_62") (pintype "bidirectional"))
    )
    (net (code "46") (name "Net-(U6-PA26)") (class "Default")
      (node (ref "JP12") (pin "1") (pinfunction "1_1") (pintype "passive"))
      (node (ref "R12") (pin "2") (pinfunction "2_2") (pintype "passive"))
      (node (ref "U6") (pin "63") (pinfunction "PA26_63") (pintype "bidirectional"))
    )
    (net (code "47") (name "Net-(U6-RESET_N)") (class "Default")
      (node (ref "C17") (pin "1") (pinfunction "1_1") (pintype "passive"))
      (node (ref "R10") (pin "1") (pinfunction "1_1") (pintype "passive"))
      (node (ref "R11") (pin "2") (pinfunction "2_2") (pintype "passive"))
      (node (ref "U6") (pin "4") (pinfunction "RESET_N_4") (pintype "bidirectional"))
    )
    (net (code "48") (name "Net-(U6-VDDOUT\\)") (class "Default")
      (node (ref "L1") (pin "2") (pinfunction "2_2") (pintype "passive"))
      (node (ref "U6") (pin "7") (pinfunction "VDDOUT\\_7") (pintype "bidirectional"))
    )
    (net (code "49") (name "Net-(U6-XIN32)") (class "Default")
      (node (ref "C8") (pin "1") (pinfunction "1_1") (pintype "passive"))
      (node (ref "Q3") (pin "1") (pinfunction "1_1") (pintype "passive"))
      (node (ref "U6") (pin "17") (pinfunction "XIN32_17") (pintype "bidirectional"))
    )
    (net (code "50") (name "Net-(U14-1A)") (class "Default")
      (node (ref "U14") (pin "2") (pinfunction "1A_2") (pintype "bidirectional"))
      (node (ref "U5") (pin "1") (pinfunction "TXD_1") (pintype "output"))
    )
    (net (code "51") (name "Net-(U14-2OE)") (class "Default")
      (node (ref "R38") (pin "1") (pinfunction "1_1") (pintype "passive"))
      (node (ref "U14") (pin "7") (pinfunction "2OE_7") (pintype "bidirectional"))
    )
    (net (code "52") (name "Net-(U14-2Y)") (class "Default")
      (node (ref "U14") (pin "3") (pinfunction "2Y_3") (pintype "bidirectional"))
      (node (ref "U5") (pin "5") (pinfunction "RXD_5") (pintype "input"))
    )
    (net (code "53") (name "PIC2") (class "Default")
      (node (ref "U14") (pin "6") (pinfunction "1Y_6") (pintype "bidirectional"))
    )
    (net (code "54") (name "PIC3") (class "Default")
      (node (ref "U14") (pin "5") (pinfunction "2A_5") (pintype "bidirectional"))
    )
    (net (code "55") (name "RS485-1-A") (class "Default")
      (node (ref "U3") (pin "8") (pinfunction "A_8") (pintype "bidirectional"))
      (node (ref "X1") (pin "21") (pinfunction "P_21") (pintype "passive"))
    )
    (net (code "56") (name "RS485-1-B") (class "Default")
      (node (ref "U3") (pin "7") (pinfunction "B_7") (pintype "bidirectional"))
      (node (ref "X1") (pin "23") (pinfunction "P_23") (pintype "passive"))
    )
    (net (code "57") (name "RS485-1-Y") (class "Default")
      (node (ref "U3") (pin "5") (pinfunction "Y_5") (pintype "bidirectional"))
      (node (ref "X1") (pin "19") (pinfunction "P_19") (pintype "passive"))
    )
    (net (code "58") (name "RS485-1-Z") (class "Default")
      (node (ref "U3") (pin "6") (pinfunction "Z_6") (pintype "bidirectional"))
      (node (ref "X1") (pin "17") (pinfunction "P_17") (pintype "passive"))
    )
    (net (code "59") (name "RS485-2-A") (class "Default")
      (node (ref "U4") (pin "8") (pinfunction "A_8") (pintype "bidirectional"))
      (node (ref "X1") (pin "29") (pinfunction "P_29") (pintype "passive"))
    )
    (net (code "60") (name "RS485-2-B") (class "Default")
      (node (ref "U4") (pin "7") (pinfunction "B_7") (pintype "bidirectional"))
      (node (ref "X1") (pin "31") (pinfunction "P_31") (pintype "passive"))
    )
    (net (code "61") (name "RS485-2-Y") (class "Default")
      (node (ref "U4") (pin "5") (pinfunction "Y_5") (pintype "bidirectional"))
      (node (ref "X1") (pin "27") (pinfunction "P_27") (pintype "passive"))
    )
    (net (code "62") (name "RS485-2-Z") (class "Default")
      (node (ref "U4") (pin "6") (pinfunction "Z_6") (pintype "bidirectional"))
      (node (ref "X1") (pin "25") (pinfunction "P_25") (pintype "passive"))
    )
    (net (code "63") (name "RS485-3-A") (class "Default")
      (node (ref "U2") (pin "8") (pinfunction "A_8") (pintype "bidirectional"))
      (node (ref "X1") (pin "37") (pinfunction "P_37") (pintype "passive"))
    )
    (net (code "64") (name "RS485-3-B") (class "Default")
      (node (ref "U2") (pin "7") (pinfunction "B_7") (pintype "bidirectional"))
      (node (ref "X1") (pin "39") (pinfunction "P_39") (pintype "passive"))
    )
    (net (code "65") (name "RS485-3-Y") (class "Default")
      (node (ref "U2") (pin "5") (pinfunction "Y_5") (pintype "bidirectional"))
      (node (ref "X1") (pin "35") (pinfunction "P_35") (pintype "passive"))
    )
    (net (code "66") (name "RS485-3-Z") (class "Default")
      (node (ref "U2") (pin "6") (pinfunction "Z_6") (pintype "bidirectional"))
      (node (ref "X1") (pin "33") (pinfunction "P_33") (pintype "passive"))
    )
    (net (code "67") (name "RS485-4-A") (class "Default")
      (node (ref "U1") (pin "8") (pinfunction "A_8") (pintype "bidirectional"))
      (node (ref "X1") (pin "47") (pinfunction "P_47") (pintype "passive"))
    )
    (net (code "68") (name "RS485-4-B") (class "Default")
      (node (ref "U1") (pin "7") (pinfunction "B_7") (pintype "bidirectional"))
      (node (ref "X1") (pin "49") (pinfunction "P_49") (pintype "passive"))
    )
    (net (code "69") (name "RS485-4-Y") (class "Default")
      (node (ref "U1") (pin "5") (pinfunction "Y_5") (pintype "bidirectional"))
      (node (ref "X1") (pin "45") (pinfunction "P_45") (pintype "passive"))
    )
    (net (code "70") (name "RS485-4-Z") (class "Default")
      (node (ref "U1") (pin "6") (pinfunction "Z_6") (pintype "bidirectional"))
      (node (ref "X1") (pin "43") (pinfunction "P_43") (pintype "passive"))
    )
    (net (code "71") (name "RTD-HORN") (class "Default")
      (node (ref "R16") (pin "2") (pinfunction "2_2") (pintype "passive"))
    )
    (net (code "72") (name "RXD1") (class "Default")
      (node (ref "JP3") (pin "2") (pinfunction "2_2") (pintype "passive"))
      (node (ref "RX1") (pin "C") (pinfunction "C_C") (pintype "passive"))
      (node (ref "U3") (pin "2") (pinfunction "RO_2") (pintype "bidirectional"))
    )
    (net (code "73") (name "RXD2") (class "Default")
      (node (ref "JP4") (pin "2") (pinfunction "2_2") (pintype "passive"))
      (node (ref "RX3") (pin "C") (pinfunction "C_C") (pintype "passive"))
      (node (ref "U4") (pin "2") (pinfunction "RO_2") (pintype "bidirectional"))
    )
    (net (code "74") (name "RXD3") (class "Default")
      (node (ref "JP2") (pin "2") (pinfunction "2_2") (pintype "passive"))
      (node (ref "RX2") (pin "C") (pinfunction "C_C") (pintype "passive"))
      (node (ref "U2") (pin "2") (pinfunction "RO_2") (pintype "bidirectional"))
    )
    (net (code "75") (name "RXD4") (class "Default")
      (node (ref "JP1") (pin "2") (pinfunction "2_2") (pintype "passive"))
      (node (ref "RX4") (pin "C") (pinfunction "C_C") (pintype "passive"))
      (node (ref "U1") (pin "2") (pinfunction "RO_2") (pintype "bidirectional"))
    )
    (net (code "76") (name "SS") (class "Default")
      (node (ref "R7") (pin "1") (pinfunction "1_1") (pintype "passive"))
    )
    (net (code "77") (name "TXD1") (class "Default")
      (node (ref "JP3") (pin "1") (pinfunction "1_1") (pintype "passive"))
      (node (ref "TX1") (pin "C") (pinfunction "C_C") (pintype "passive"))
      (node (ref "U3") (pin "3") (pinfunction "DI_3") (pintype "bidirectional"))
    )
    (net (code "78") (name "TXD2") (class "Default")
      (node (ref "JP4") (pin "1") (pinfunction "1_1") (pintype "passive"))
      (node (ref "TX3") (pin "C") (pinfunction "C_C") (pintype "passive"))
      (node (ref "U4") (pin "3") (pinfunction "DI_3") (pintype "bidirectional"))
    )
    (net (code "79") (name "TXD3") (class "Default")
      (node (ref "JP2") (pin "1") (pinfunction "1_1") (pintype "passive"))
      (node (ref "TX2") (pin "C") (pinfunction "C_C") (pintype "passive"))
      (node (ref "U2") (pin "3") (pinfunction "DI_3") (pintype "bidirectional"))
    )
    (net (code "80") (name "TXD4") (class "Default")
      (node (ref "JP1") (pin "1") (pinfunction "1_1") (pintype "passive"))
      (node (ref "TX4") (pin "C") (pinfunction "C_C") (pintype "passive"))
      (node (ref "U1") (pin "3") (pinfunction "DI_3") (pintype "bidirectional"))
    )
    (net (code "81") (name "U1RX") (class "Default")
      (node (ref "U6") (pin "57") (pinfunction "PB14_57") (pintype "bidirectional"))
    )
    (net (code "82") (name "U1TX") (class "Default")
      (node (ref "U6") (pin "58") (pinfunction "PB15_58") (pintype "bidirectional"))
    )
    (net (code "83") (name "U3RX") (class "Default")
      (node (ref "U6") (pin "46") (pinfunction "PB09_46") (pintype "bidirectional"))
    )
    (net (code "84") (name "U3TX") (class "Default")
      (node (ref "U6") (pin "47") (pinfunction "PB10_47") (pintype "bidirectional"))
    )
    (net (code "85") (name "VBUSD") (class "Default")
      (node (ref "JP17") (pin "1") (pinfunction "1_1") (pintype "passive"))
      (node (ref "R14") (pin "1") (pinfunction "1_1") (pintype "passive"))
      (node (ref "R15") (pin "2") (pinfunction "2_2") (pintype "passive"))
    )
    (net (code "86") (name "VUSB") (class "Default")
      (node (ref "CN2") (pin "VBUS") (pinfunction "VBUS_VBUS") (pintype "power_in"))
      (node (ref "JP18") (pin "1") (pinfunction "1_1") (pintype "passive"))
      (node (ref "R14") (pin "2") (pinfunction "2_2") (pintype "passive"))
    )
    (net (code "87") (name "unconnected-(CN1-PadID)") (class "Default")
      (node (ref "CN1") (pin "ID") (pinfunction "ID_ID") (pintype "bidirectional"))
    )
    (net (code "88") (name "unconnected-(CN2-PadID)") (class "Default")
      (node (ref "CN2") (pin "ID") (pinfunction "ID_ID") (pintype "bidirectional"))
    )
    (net (code "89") (name "unconnected-(JP13-1-PadDTR)") (class "Default")
      (node (ref "JP13") (pin "DTR") (pinfunction "1_DTR") (pintype "passive"))
    )
    (net (code "90") (name "unconnected-(JP13-2-PadRXI)") (class "Default")
      (node (ref "JP13") (pin "RXI") (pinfunction "2_RXI") (pintype "passive"))
    )
    (net (code "91") (name "unconnected-(JP13-3-PadTXO)") (class "Default")
      (node (ref "JP13") (pin "TXO") (pinfunction "3_TXO") (pintype "passive"))
    )
    (net (code "92") (name "unconnected-(JP13-4-PadVCC)") (class "Default")
      (node (ref "JP13") (pin "VCC") (pinfunction "4_VCC") (pintype "passive"))
    )
    (net (code "93") (name "unconnected-(JP13-5-PadCTS)") (class "Default")
      (node (ref "JP13") (pin "CTS") (pinfunction "5_CTS") (pintype "passive"))
    )
    (net (code "94") (name "unconnected-(U5-CTS-Pad11)") (class "Default")
      (node (ref "U5") (pin "11") (pinfunction "CTS_11") (pintype "bidirectional"))
    )
    (net (code "95") (name "unconnected-(U5-DTR-Pad2)") (class "Default")
      (node (ref "U5") (pin "2") (pinfunction "DTR_2") (pintype "bidirectional"))
    )
    (net (code "96") (name "unconnected-(U5-RTS-Pad3)") (class "Default")
      (node (ref "U5") (pin "3") (pinfunction "RTS_3") (pintype "bidirectional"))
    )
    (net (code "97") (name "unconnected-(U6-PA04-Pad15)") (class "Default")
      (node (ref "U6") (pin "15") (pinfunction "PA04_15") (pintype "bidirectional"))
    )
    (net (code "98") (name "unconnected-(U6-PA05-Pad16)") (class "Default")
      (node (ref "U6") (pin "16") (pinfunction "PA05_16") (pintype "bidirectional"))
    )
    (net (code "99") (name "unconnected-(U6-PA06-Pad21)") (class "Default")
      (node (ref "U6") (pin "21") (pinfunction "PA06_21") (pintype "bidirectional"))
    )
    (net (code "100") (name "unconnected-(U6-PA07-Pad22)") (class "Default")
      (node (ref "U6") (pin "22") (pinfunction "PA07_22") (pintype "bidirectional"))
    )
    (net (code "101") (name "unconnected-(U6-PA08-Pad26)") (class "Default")
      (node (ref "U6") (pin "26") (pinfunction "PA08_26") (pintype "bidirectional"))
    )
    (net (code "102") (name "unconnected-(U6-PA09-Pad29)") (class "Default")
      (node (ref "U6") (pin "29") (pinfunction "PA09_29") (pintype "bidirectional"))
    )
    (net (code "103") (name "unconnected-(U6-PA10-Pad30)") (class "Default")
      (node (ref "U6") (pin "30") (pinfunction "PA10_30") (pintype "bidirectional"))
    )
    (net (code "104") (name "unconnected-(U6-PA11-Pad31)") (class "Default")
      (node (ref "U6") (pin "31") (pinfunction "PA11_31") (pintype "bidirectional"))
    )
    (net (code "105") (name "unconnected-(U6-PA12-Pad32)") (class "Default")
      (node (ref "U6") (pin "32") (pinfunction "PA12_32") (pintype "bidirectional"))
    )
    (net (code "106") (name "unconnected-(U6-PA13-Pad40)") (class "Default")
      (node (ref "U6") (pin "40") (pinfunction "PA13_40") (pintype "bidirectional"))
    )
    (net (code "107") (name "unconnected-(U6-PA14-Pad41)") (class "Default")
      (node (ref "U6") (pin "41") (pinfunction "PA14_41") (pintype "bidirectional"))
    )
    (net (code "108") (name "unconnected-(U6-PA15-Pad42)") (class "Default")
      (node (ref "U6") (pin "42") (pinfunction "PA15_42") (pintype "bidirectional"))
    )
    (net (code "109") (name "unconnected-(U6-PA16-Pad43)") (class "Default")
      (node (ref "U6") (pin "43") (pinfunction "PA16_43") (pintype "bidirectional"))
    )
    (net (code "110") (name "unconnected-(U6-PA17-Pad44)") (class "Default")
      (node (ref "U6") (pin "44") (pinfunction "PA17_44") (pintype "bidirectional"))
    )
    (net (code "111") (name "unconnected-(U6-PA18-Pad49)") (class "Default")
      (node (ref "U6") (pin "49") (pinfunction "PA18_49") (pintype "bidirectional"))
    )
    (net (code "112") (name "unconnected-(U6-PA19-Pad50)") (class "Default")
      (node (ref "U6") (pin "50") (pinfunction "PA19_50") (pintype "bidirectional"))
    )
    (net (code "113") (name "unconnected-(U6-PA20-Pad51)") (class "Default")
      (node (ref "U6") (pin "51") (pinfunction "PA20_51") (pintype "bidirectional"))
    )
    (net (code "114") (name "unconnected-(U6-PA27-Pad33)") (class "Default")
      (node (ref "U6") (pin "33") (pinfunction "PA27_33") (pintype "bidirectional"))
    )
    (net (code "115") (name "unconnected-(U6-PA28-Pad34)") (class "Default")
      (node (ref "U6") (pin "34") (pinfunction "PA28_34") (pintype "bidirectional"))
    )
    (net (code "116") (name "unconnected-(U6-PA29-Pad35)") (class "Default")
      (node (ref "U6") (pin "35") (pinfunction "PA29_35") (pintype "bidirectional"))
    )
    (net (code "117") (name "unconnected-(U6-PA30-Pad38)") (class "Default")
      (node (ref "U6") (pin "38") (pinfunction "PA30_38") (pintype "bidirectional"))
    )
    (net (code "118") (name "unconnected-(U6-PA31-Pad39)") (class "Default")
      (node (ref "U6") (pin "39") (pinfunction "PA31_39") (pintype "bidirectional"))
    )
    (net (code "119") (name "unconnected-(U6-PB00-Pad11)") (class "Default")
      (node (ref "U6") (pin "11") (pinfunction "PB00_11") (pintype "bidirectional"))
    )
    (net (code "120") (name "unconnected-(U6-PB01-Pad12)") (class "Default")
      (node (ref "U6") (pin "12") (pinfunction "PB01_12") (pintype "bidirectional"))
    )
    (net (code "121") (name "unconnected-(U6-PB02-Pad13)") (class "Default")
      (node (ref "U6") (pin "13") (pinfunction "PB02_13") (pintype "bidirectional"))
    )
    (net (code "122") (name "unconnected-(U6-PB03-Pad14)") (class "Default")
      (node (ref "U6") (pin "14") (pinfunction "PB03_14") (pintype "bidirectional"))
    )
    (net (code "123") (name "unconnected-(U6-PB04-Pad19)") (class "Default")
      (node (ref "U6") (pin "19") (pinfunction "PB04_19") (pintype "bidirectional"))
    )
    (net (code "124") (name "unconnected-(U6-PB05-Pad20)") (class "Default")
      (node (ref "U6") (pin "20") (pinfunction "PB05_20") (pintype "bidirectional"))
    )
    (net (code "125") (name "unconnected-(U6-PB06-Pad27)") (class "Default")
      (node (ref "U6") (pin "27") (pinfunction "PB06_27") (pintype "bidirectional"))
    )
    (net (code "126") (name "unconnected-(U6-PB07-Pad28)") (class "Default")
      (node (ref "U6") (pin "28") (pinfunction "PB07_28") (pintype "bidirectional"))
    )
    (net (code "127") (name "unconnected-(U6-PB08-Pad45)") (class "Default")
      (node (ref "U6") (pin "45") (pinfunction "PB08_45") (pintype "bidirectional"))
    )
    (net (code "128") (name "unconnected-(U6-PB11-Pad48)") (class "Default")
      (node (ref "U6") (pin "48") (pinfunction "PB11_48") (pintype "bidirectional"))
    )
    (net (code "129") (name "unconnected-(U6-PB12-Pad53)") (class "Default")
      (node (ref "U6") (pin "53") (pinfunction "PB12_53") (pintype "bidirectional"))
    )
    (net (code "130") (name "unconnected-(U6-PB13-Pad54)") (class "Default")
      (node (ref "U6") (pin "54") (pinfunction "PB13_54") (pintype "bidirectional"))
    )
    (net (code "131") (name "unconnected-(U6-TCK-Pad9)") (class "Default")
      (node (ref "U6") (pin "9") (pinfunction "TCK_9") (pintype "bidirectional"))
    )
    (net (code "132") (name "unconnected-(U14-GND-Pad4)") (class "Default")
      (node (ref "U14") (pin "4") (pinfunction "GND_4") (pintype "bidirectional"))
    )
    (net (code "133") (name "unconnected-(X1AI-P-Pad18)") (class "Default")
      (node (ref "X1") (pin "18") (pinfunction "P_18") (pintype "passive"))
    )
    (net (code "134") (name "unconnected-(X1AL-P-Pad20)") (class "Default")
      (node (ref "X1") (pin "20") (pinfunction "P_20") (pintype "passive"))
    )
    (net (code "135") (name "unconnected-(X1AN-P-Pad22)") (class "Default")
      (node (ref "X1") (pin "22") (pinfunction "P_22") (pintype "passive"))
    )
    (net (code "136") (name "unconnected-(X1AP-P-Pad24)") (class "Default")
      (node (ref "X1") (pin "24") (pinfunction "P_24") (pintype "passive"))
    )
    (net (code "137") (name "unconnected-(X1AR-P-Pad26)") (class "Default")
      (node (ref "X1") (pin "26") (pinfunction "P_26") (pintype "passive"))
    )
    (net (code "138") (name "unconnected-(X1AT-P-Pad28)") (class "Default")
      (node (ref "X1") (pin "28") (pinfunction "P_28") (pintype "passive"))
    )
    (net (code "139") (name "unconnected-(X1AW-P-Pad30)") (class "Default")
      (node (ref "X1") (pin "30") (pinfunction "P_30") (pintype "passive"))
    )
    (net (code "140") (name "unconnected-(X1AY-P-Pad32)") (class "Default")
      (node (ref "X1") (pin "32") (pinfunction "P_32") (pintype "passive"))
    )
    (net (code "141") (name "unconnected-(X1BA-P-Pad34)") (class "Default")
      (node (ref "X1") (pin "34") (pinfunction "P_34") (pintype "passive"))
    )
    (net (code "142") (name "unconnected-(X1BC-P-Pad36)") (class "Default")
      (node (ref "X1") (pin "36") (pinfunction "P_36") (pintype "passive"))
    )
    (net (code "143") (name "unconnected-(X1BE-P-Pad38)") (class "Default")
      (node (ref "X1") (pin "38") (pinfunction "P_38") (pintype "passive"))
    )
    (net (code "144") (name "unconnected-(X1BH-P-Pad40)") (class "Default")
      (node (ref "X1") (pin "40") (pinfunction "P_40") (pintype "passive"))
    )
    (net (code "145") (name "unconnected-(X1BI-P-Pad41)") (class "Default")
      (node (ref "X1") (pin "41") (pinfunction "P_41") (pintype "passive"))
    )
    (net (code "146") (name "unconnected-(X1BJ-P-Pad42)") (class "Default")
      (node (ref "X1") (pin "42") (pinfunction "P_42") (pintype "passive"))
    )
    (net (code "147") (name "unconnected-(X1BL-P-Pad44)") (class "Default")
      (node (ref "X1") (pin "44") (pinfunction "P_44") (pintype "passive"))
    )
    (net (code "148") (name "unconnected-(X1BN-P-Pad46)") (class "Default")
      (node (ref "X1") (pin "46") (pinfunction "P_46") (pintype "passive"))
    )
    (net (code "149") (name "unconnected-(X1BP-P-Pad48)") (class "Default")
      (node (ref "X1") (pin "48") (pinfunction "P_48") (pintype "passive"))
    )
    (net (code "150") (name "unconnected-(X1BS-P-Pad50)") (class "Default")
      (node (ref "X1") (pin "50") (pinfunction "P_50") (pintype "passive"))
    )
    (net (code "151") (name "unconnected-(X1BT-P-Pad51)") (class "Default")
      (node (ref "X1") (pin "51") (pinfunction "P_51") (pintype "passive"))
    )
    (net (code "152") (name "unconnected-(X1BU-P-Pad52)") (class "Default")
      (node (ref "X1") (pin "52") (pinfunction "P_52") (pintype "passive"))
    )
    (net (code "153") (name "unconnected-(X1BV-P-Pad53)") (class "Default")
      (node (ref "X1") (pin "53") (pinfunction "P_53") (pintype "passive"))
    )
    (net (code "154") (name "unconnected-(X1BW-P-Pad54)") (class "Default")
      (node (ref "X1") (pin "54") (pinfunction "P_54") (pintype "passive"))
    )
    (net (code "155") (name "unconnected-(X1BX-P-Pad55)") (class "Default")
      (node (ref "X1") (pin "55") (pinfunction "P_55") (pintype "passive"))
    )
    (net (code "156") (name "unconnected-(X1BY-P-Pad56)") (class "Default")
      (node (ref "X1") (pin "56") (pinfunction "P_56") (pintype "passive"))
    )
    (net (code "157") (name "unconnected-(X1BZ-P-Pad57)") (class "Default")
      (node (ref "X1") (pin "57") (pinfunction "P_57") (pintype "passive"))
    )
    (net (code "158") (name "unconnected-(X1C-P-Pad100)") (class "Default")
      (node (ref "X1") (pin "100") (pinfunction "P_100") (pintype "passive"))
    )
    (net (code "159") (name "unconnected-(X1CA-P-Pad58)") (class "Default")
      (node (ref "X1") (pin "58") (pinfunction "P_58") (pintype "passive"))
    )
    (net (code "160") (name "unconnected-(X1CB-P-Pad59)") (class "Default")
      (node (ref "X1") (pin "59") (pinfunction "P_59") (pintype "passive"))
    )
    (net (code "161") (name "unconnected-(X1CD-P-Pad60)") (class "Default")
      (node (ref "X1") (pin "60") (pinfunction "P_60") (pintype "passive"))
    )
    (net (code "162") (name "unconnected-(X1CE-P-Pad61)") (class "Default")
      (node (ref "X1") (pin "61") (pinfunction "P_61") (pintype "passive"))
    )
    (net (code "163") (name "unconnected-(X1CF-P-Pad62)") (class "Default")
      (node (ref "X1") (pin "62") (pinfunction "P_62") (pintype "passive"))
    )
    (net (code "164") (name "unconnected-(X1CG-P-Pad63)") (class "Default")
      (node (ref "X1") (pin "63") (pinfunction "P_63") (pintype "passive"))
    )
    (net (code "165") (name "unconnected-(X1CH-P-Pad64)") (class "Default")
      (node (ref "X1") (pin "64") (pinfunction "P_64") (pintype "passive"))
    )
    (net (code "166") (name "unconnected-(X1CI-P-Pad65)") (class "Default")
      (node (ref "X1") (pin "65") (pinfunction "P_65") (pintype "passive"))
    )
    (net (code "167") (name "unconnected-(X1CJ-P-Pad66)") (class "Default")
      (node (ref "X1") (pin "66") (pinfunction "P_66") (pintype "passive"))
    )
    (net (code "168") (name "unconnected-(X1CK-P-Pad67)") (class "Default")
      (node (ref "X1") (pin "67") (pinfunction "P_67") (pintype "passive"))
    )
    (net (code "169") (name "unconnected-(X1CL-P-Pad68)") (class "Default")
      (node (ref "X1") (pin "68") (pinfunction "P_68") (pintype "passive"))
    )
    (net (code "170") (name "unconnected-(X1CM-P-Pad69)") (class "Default")
      (node (ref "X1") (pin "69") (pinfunction "P_69") (pintype "passive"))
    )
    (net (code "171") (name "unconnected-(X1CO-P-Pad70)") (class "Default")
      (node (ref "X1") (pin "70") (pinfunction "P_70") (pintype "passive"))
    )
    (net (code "172") (name "unconnected-(X1CP-P-Pad71)") (class "Default")
      (node (ref "X1") (pin "71") (pinfunction "P_71") (pintype "passive"))
    )
    (net (code "173") (name "unconnected-(X1CQ-P-Pad72)") (class "Default")
      (node (ref "X1") (pin "72") (pinfunction "P_72") (pintype "passive"))
    )
    (net (code "174") (name "unconnected-(X1CR-P-Pad73)") (class "Default")
      (node (ref "X1") (pin "73") (pinfunction "P_73") (pintype "passive"))
    )
    (net (code "175") (name "unconnected-(X1CS-P-Pad74)") (class "Default")
      (node (ref "X1") (pin "74") (pinfunction "P_74") (pintype "passive"))
    )
    (net (code "176") (name "unconnected-(X1CT-P-Pad75)") (class "Default")
      (node (ref "X1") (pin "75") (pinfunction "P_75") (pintype "passive"))
    )
    (net (code "177") (name "unconnected-(X1CU-P-Pad76)") (class "Default")
      (node (ref "X1") (pin "76") (pinfunction "P_76") (pintype "passive"))
    )
    (net (code "178") (name "unconnected-(X1CV-P-Pad77)") (class "Default")
      (node (ref "X1") (pin "77") (pinfunction "P_77") (pintype "passive"))
    )
    (net (code "179") (name "unconnected-(X1CW-P-Pad78)") (class "Default")
      (node (ref "X1") (pin "78") (pinfunction "P_78") (pintype "passive"))
    )
    (net (code "180") (name "unconnected-(X1CX-P-Pad79)") (class "Default")
      (node (ref "X1") (pin "79") (pinfunction "P_79") (pintype "passive"))
    )
    (net (code "181") (name "unconnected-(X1CZ-P-Pad80)") (class "Default")
      (node (ref "X1") (pin "80") (pinfunction "P_80") (pintype "passive"))
    )
    (net (code "182") (name "unconnected-(X1D-P-Pad101)") (class "Default")
      (node (ref "X1") (pin "101") (pinfunction "P_101") (pintype "passive"))
    )
    (net (code "183") (name "unconnected-(X1DA-P-Pad81)") (class "Default")
      (node (ref "X1") (pin "81") (pinfunction "P_81") (pintype "passive"))
    )
    (net (code "184") (name "unconnected-(X1DB-P-Pad82)") (class "Default")
      (node (ref "X1") (pin "82") (pinfunction "P_82") (pintype "passive"))
    )
    (net (code "185") (name "unconnected-(X1DC-P-Pad83)") (class "Default")
      (node (ref "X1") (pin "83") (pinfunction "P_83") (pintype "passive"))
    )
    (net (code "186") (name "unconnected-(X1DD-P-Pad84)") (class "Default")
      (node (ref "X1") (pin "84") (pinfunction "P_84") (pintype "passive"))
    )
    (net (code "187") (name "unconnected-(X1DE-P-Pad85)") (class "Default")
      (node (ref "X1") (pin "85") (pinfunction "P_85") (pintype "passive"))
    )
    (net (code "188") (name "unconnected-(X1DF-P-Pad86)") (class "Default")
      (node (ref "X1") (pin "86") (pinfunction "P_86") (pintype "passive"))
    )
    (net (code "189") (name "unconnected-(X1DG-P-Pad87)") (class "Default")
      (node (ref "X1") (pin "87") (pinfunction "P_87") (pintype "passive"))
    )
    (net (code "190") (name "unconnected-(X1DH-P-Pad88)") (class "Default")
      (node (ref "X1") (pin "88") (pinfunction "P_88") (pintype "passive"))
    )
    (net (code "191") (name "unconnected-(X1DI-P-Pad89)") (class "Default")
      (node (ref "X1") (pin "89") (pinfunction "P_89") (pintype "passive"))
    )
    (net (code "192") (name "unconnected-(X1DK-P-Pad90)") (class "Default")
      (node (ref "X1") (pin "90") (pinfunction "P_90") (pintype "passive"))
    )
    (net (code "193") (name "unconnected-(X1DL-P-Pad91)") (class "Default")
      (node (ref "X1") (pin "91") (pinfunction "P_91") (pintype "passive"))
    )
    (net (code "194") (name "unconnected-(X1DM-P-Pad92)") (class "Default")
      (node (ref "X1") (pin "92") (pinfunction "P_92") (pintype "passive"))
    )
    (net (code "195") (name "unconnected-(X1DN-P-Pad93)") (class "Default")
      (node (ref "X1") (pin "93") (pinfunction "P_93") (pintype "passive"))
    )
    (net (code "196") (name "unconnected-(X1DO-P-Pad94)") (class "Default")
      (node (ref "X1") (pin "94") (pinfunction "P_94") (pintype "passive"))
    )
    (net (code "197") (name "unconnected-(X1DP-P-Pad95)") (class "Default")
      (node (ref "X1") (pin "95") (pinfunction "P_95") (pintype "passive"))
    )
    (net (code "198") (name "unconnected-(X1DQ-P-Pad96)") (class "Default")
      (node (ref "X1") (pin "96") (pinfunction "P_96") (pintype "passive"))
    )
    (net (code "199") (name "unconnected-(X1DR-P-Pad97)") (class "Default")
      (node (ref "X1") (pin "97") (pinfunction "P_97") (pintype "passive"))
    )
    (net (code "200") (name "unconnected-(X1DS-P-Pad98)") (class "Default")
      (node (ref "X1") (pin "98") (pinfunction "P_98") (pintype "passive"))
    )
    (net (code "201") (name "unconnected-(X1DT-P-Pad99)") (class "Default")
      (node (ref "X1") (pin "99") (pinfunction "P_99") (pintype "passive"))
    )
    (net (code "202") (name "unconnected-(X1E-P-Pad102)") (class "Default")
      (node (ref "X1") (pin "102") (pinfunction "P_102") (pintype "passive"))
    )
    (net (code "203") (name "unconnected-(X1F-P-Pad103)") (class "Default")
      (node (ref "X1") (pin "103") (pinfunction "P_103") (pintype "passive"))
    )
    (net (code "204") (name "unconnected-(X1G-P-Pad104)") (class "Default")
      (node (ref "X1") (pin "104") (pinfunction "P_104") (pintype "passive"))
    )
    (net (code "205") (name "unconnected-(X1H-P-Pad105)") (class "Default")
      (node (ref "X1") (pin "105") (pinfunction "P_105") (pintype "passive"))
    )
    (net (code "206") (name "unconnected-(X1I-P-Pad106)") (class "Default")
      (node (ref "X1") (pin "106") (pinfunction "P_106") (pintype "passive"))
    )
    (net (code "207") (name "unconnected-(X1J-P-Pad107)") (class "Default")
      (node (ref "X1") (pin "107") (pinfunction "P_107") (pintype "passive"))
    )
    (net (code "208") (name "unconnected-(X1K-P-Pad108)") (class "Default")
      (node (ref "X1") (pin "108") (pinfunction "P_108") (pintype "passive"))
    )
    (net (code "209") (name "unconnected-(X1L-P-Pad109)") (class "Default")
      (node (ref "X1") (pin "109") (pinfunction "P_109") (pintype "passive"))
    )
    (net (code "210") (name "unconnected-(X1N-P-Pad110)") (class "Default")
      (node (ref "X1") (pin "110") (pinfunction "P_110") (pintype "passive"))
    )
    (net (code "211") (name "unconnected-(X1O-P-Pad111)") (class "Default")
      (node (ref "X1") (pin "111") (pinfunction "P_111") (pintype "passive"))
    )
    (net (code "212") (name "unconnected-(X1P-P-Pad112)") (class "Default")
      (node (ref "X1") (pin "112") (pinfunction "P_112") (pintype "passive"))
    )
    (net (code "213") (name "unconnected-(X1Q-P-Pad113)") (class "Default")
      (node (ref "X1") (pin "113") (pinfunction "P_113") (pintype "passive"))
    )
    (net (code "214") (name "unconnected-(X1R-P-Pad114)") (class "Default")
      (node (ref "X1") (pin "114") (pinfunction "P_114") (pintype "passive"))
    )
    (net (code "215") (name "unconnected-(X1S-P-Pad115)") (class "Default")
      (node (ref "X1") (pin "115") (pinfunction "P_115") (pintype "passive"))
    )
    (net (code "216") (name "unconnected-(X1T-P-Pad116)") (class "Default")
      (node (ref "X1") (pin "116") (pinfunction "P_116") (pintype "passive"))
    )
  )
)
